# Sheet1.net
KiCad netlist of a schematic drawn in Altium Designer
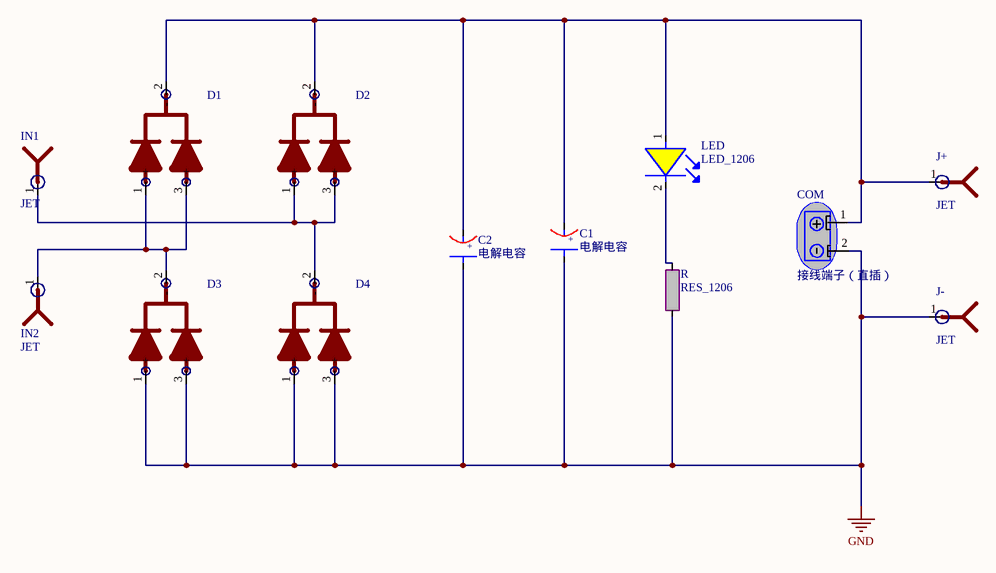
[diagram p0: Sheet1.SchDoc]

(export (version "E")
  (design (tool "Eeschema 10.0.6"))
  (components
    (comp (ref "C1") (value "电解电容") (footprint "电解电容直插") (libsource (lib "LTC_Library1") (part "电解电容")))
    (comp (ref "C2") (value "电解电容") (footprint "电解电容直插") (libsource (lib "LTC_Library1") (part "电解电容")))
    (comp (ref "COM")
      (value "接线端子（直插）")
      (footprint "接线端子直插")
      (libsource (lib "LTC_Library1") (part "接线端子（直插）"))
    )
    (comp (ref "D1")
      (value "肖特基二极管")
      (footprint "TO-220(带散热片)")
      (libsource (lib "LTC_Library1") (part "肖特基二极管"))
    )
    (comp (ref "D2")
      (value "肖特基二极管")
      (footprint "TO-220(带散热片)")
      (libsource (lib "LTC_Library1") (part "肖特基二极管"))
    )
    (comp (ref "D3")
      (value "肖特基二极管")
      (footprint "TO-220(带散热片)")
      (libsource (lib "LTC_Library1") (part "肖特基二极管"))
    )
    (comp (ref "D4")
      (value "肖特基二极管")
      (footprint "TO-220(带散热片)")
      (libsource (lib "LTC_Library1") (part "肖特基二极管"))
    )
    (comp (ref "IN1") (value "JET") (footprint "JET") (libsource (lib "LTC_Library1") (part "JET")))
    (comp (ref "IN2") (value "JET") (footprint "JET") (libsource (lib "LTC_Library1") (part "JET")))
    (comp (ref "J+") (value "JET") (footprint "JET") (libsource (lib "LTC_Library1") (part "JET")))
    (comp (ref "J-") (value "JET") (footprint "JET") (libsource (lib "LTC_Library1") (part "JET")))
    (comp (ref "LED")
      (value "LED_1206")
      (footprint "LED_1206")
      (libsource (lib "LTC_Library1") (part "LED_1206"))
    )
    (comp (ref "R")
      (value "RES_1206")
      (footprint "1206_R")
      (libsource (lib "LTC_Library1") (part "RES_1206"))
    )
  )
  (nets
    (net (code "1") (name "GND") (class "Default")
      (node (ref "C1") (pin "2") (pintype "passive"))
      (node (ref "C2") (pin "2") (pintype "passive"))
      (node (ref "COM") (pin "2") (pinfunction "GND_2") (pintype "passive"))
      (node (ref "D3") (pin "1") (pinfunction "+_1") (pintype "passive"))
      (node (ref "D3") (pin "3") (pinfunction "+_3") (pintype "passive"))
      (node (ref "D4") (pin "1") (pinfunction "+_1") (pintype "passive"))
      (node (ref "D4") (pin "3") (pinfunction "+_3") (pintype "passive"))
      (node (ref "J-") (pin "1") (pintype "passive"))
      (node (ref "R") (pin "1") (pintype "passive"))
    )
    (net (code "2") (name "Net-(COM-VCC)") (class "Default")
      (node (ref "C1") (pin "1") (pintype "passive"))
      (node (ref "C2") (pin "1") (pintype "passive"))
      (node (ref "COM") (pin "1") (pinfunction "VCC_1") (pintype "passive"))
      (node (ref "D1") (pin "2") (pinfunction "-_2") (pintype "passive"))
      (node (ref "D2") (pin "2") (pinfunction "-_2") (pintype "passive"))
      (node (ref "J+") (pin "1") (pintype "passive"))
      (node (ref "LED") (pin "1") (pintype "passive"))
    )
    (net (code "3") (name "Net-(D3--)") (class "Default")
      (node (ref "D1") (pin "1") (pinfunction "+_1") (pintype "passive"))
      (node (ref "D1") (pin "3") (pinfunction "+_3") (pintype "passive"))
      (node (ref "D3") (pin "2") (pinfunction "-_2") (pintype "passive"))
      (node (ref "IN2") (pin "1") (pintype "passive"))
    )
    (net (code "4") (name "Net-(D4--)") (class "Default")
      (node (ref "D2") (pin "1") (pinfunction "+_1") (pintype "passive"))
      (node (ref "D2") (pin "3") (pinfunction "+_3") (pintype "passive"))
      (node (ref "D4") (pin "2") (pinfunction "-_2") (pintype "passive"))
      (node (ref "IN1") (pin "1") (pintype "passive"))
    )
    (net (code "5") (name "Net-(LED-Pad2)") (class "Default")
      (node (ref "LED") (pin "2") (pintype "passive"))
      (node (ref "R") (pin "2") (pintype "passive"))
    )
  )
)
